# fpga_io_bank_0.net
KiCad netlist of a schematic drawn in Altium Designer
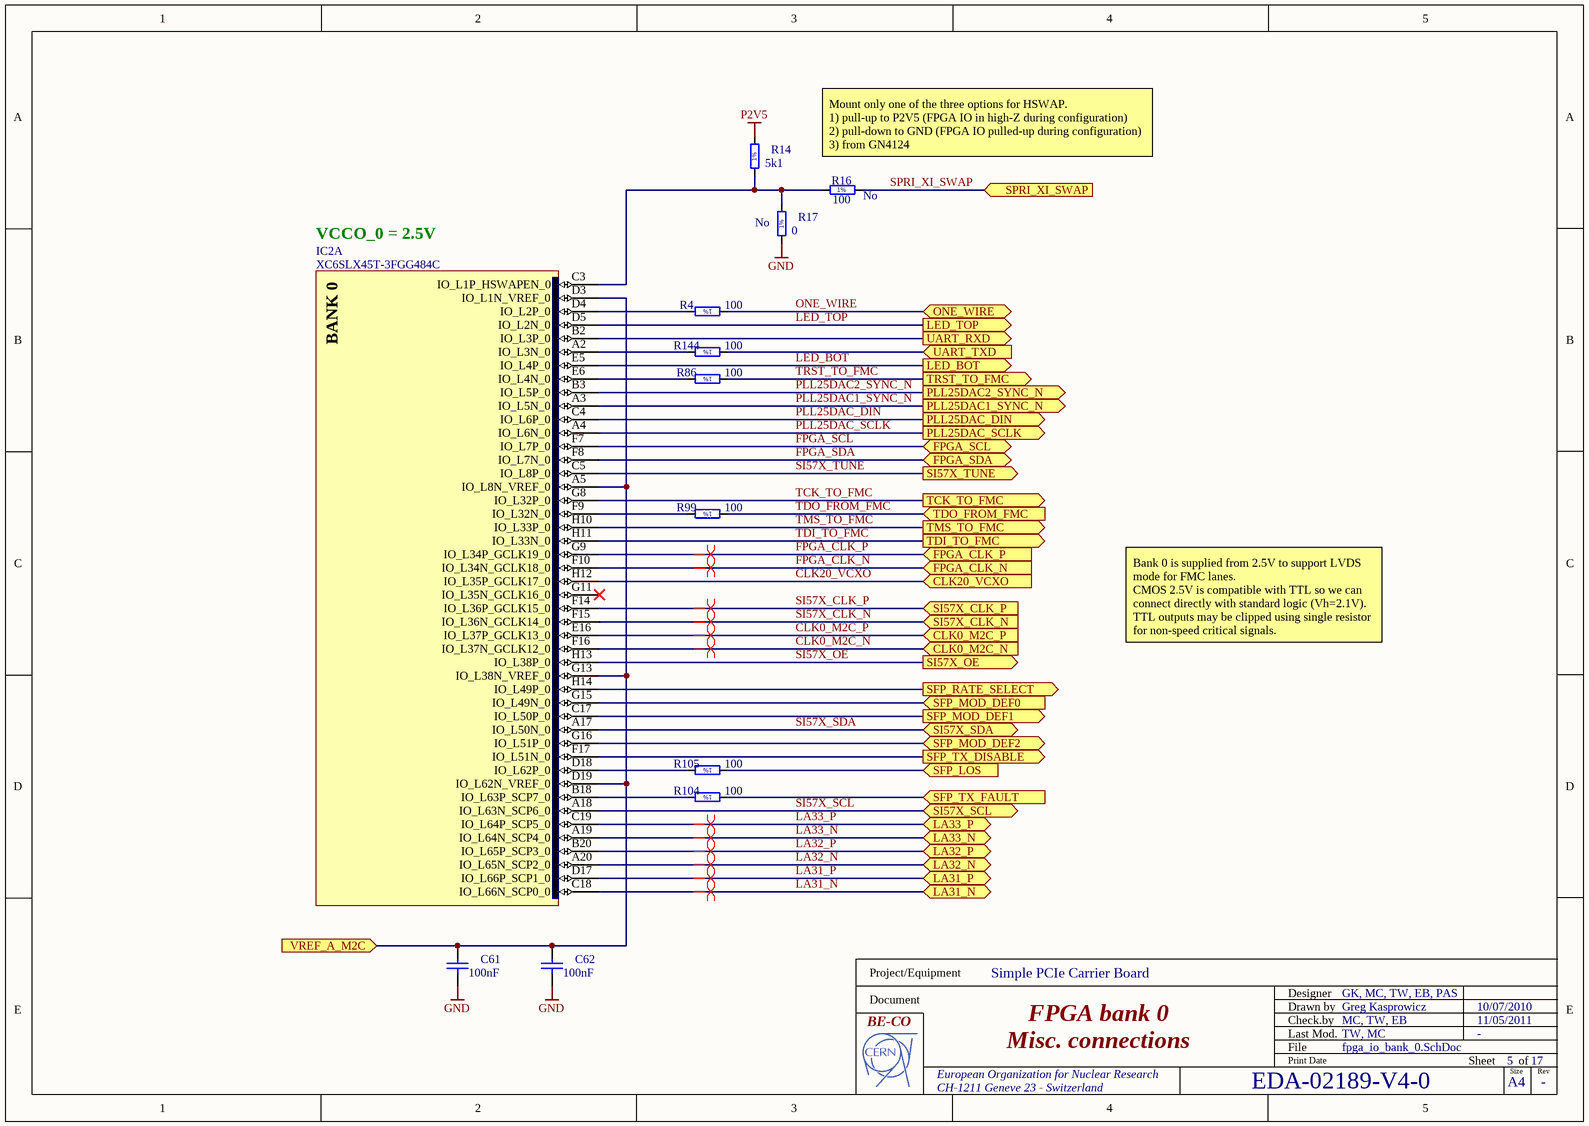
[diagram p0: fpga_io_bank_0.SchDoc]

(export (version "E")
  (design (tool "Eeschema 10.0.6"))
  (components
    (comp (ref "C61")
      (value "100nF")
      (footprint "CAPC1005X55N")
      (description "Non-polarised capacitor")
      (fields
        (field (name "PART NUMBER") "CC0402_100NF_16V_10%_X7R")
        (field (name "VOLTAGE") "16V")
        (field (name "AUTHOR") "CERN DEM JLC")
      )
      (libsource (lib "Capacitors") (part "Capacitor - non polarized"))
    )
    (comp (ref "C62")
      (value "100nF")
      (footprint "CAPC1005X55N")
      (description "Non-polarised capacitor")
      (fields
        (field (name "PART NUMBER") "CC0402_100NF_16V_10%_X7R")
        (field (name "VOLTAGE") "16V")
        (field (name "AUTHOR") "CERN DEM JLC")
      )
      (libsource (lib "Capacitors") (part "Capacitor - non polarized"))
    )
    (comp (ref "IC2")
      (value "XC6SLX45T-3FGG484C")
      (footprint "BGA484C100P22X22_2300X2300X260")
      (fields (field (name "MANUFACTURER") "XILINX") (field (name "AUTHOR") "CERN DEM JLC"))
      (libsource (lib "ICs And Semiconductors") (part "XC6SLX45T-3FGG484C"))
    )
    (comp (ref "R4")
      (value "100")
      (footprint "RESC1608X55N")
      (description "Resistor - 1%")
      (fields
        (field (name "PART NUMBER") "R0603_100R_1%_0.1W_100PPM")
        (field (name "POWER") "0.1W")
        (field (name "AUTHOR") "CERN DEM JLC")
      )
      (libsource (lib "Resistors") (part "Resistor - 1%"))
    )
    (comp (ref "R14")
      (value "5k1")
      (footprint "RESC1608X55N")
      (description "Resistor - 1%")
      (fields
        (field (name "PART NUMBER") "R0603_5K1_1%_0.1W_100PPM")
        (field (name "POWER") "0.1W")
        (field (name "AUTHOR") "CERN DEM JLC")
      )
      (libsource (lib "Resistors") (part "Resistor - 1%"))
    )
    (comp (ref "R16")
      (value "100")
      (footprint "RESC1608X55N")
      (description "Resistor - 1%")
      (fields
        (field (name "PART NUMBER") "R0603_100R_1%_0.1W_100PPM")
        (field (name "POWER") "0.1W")
        (field (name "MOUNTED") "No")
        (field (name "AUTHOR") "CERN DEM JLC")
      )
      (libsource (lib "Resistors") (part "Resistor - 1%"))
    )
    (comp (ref "R17")
      (value "0")
      (footprint "RESC1608X55N")
      (description "Resistor - 1%")
      (fields
        (field (name "PART NUMBER") "R0603_0R_JUMPER")
        (field (name "MANUFACTURER") "GENERIC")
        (field (name "MOUNTED") "No")
        (field (name "AUTHOR") "CERN DEM JLC")
      )
      (libsource (lib "Resistors") (part "Resistor - 1%"))
    )
    (comp (ref "R86")
      (value "100")
      (footprint "RESC1608X55N")
      (description "Resistor - 1%")
      (fields
        (field (name "PART NUMBER") "R0603_100R_1%_0.1W_100PPM")
        (field (name "POWER") "0.1W")
        (field (name "AUTHOR") "CERN DEM JLC")
      )
      (libsource (lib "Resistors") (part "Resistor - 1%"))
    )
    (comp (ref "R99")
      (value "100")
      (footprint "RESC1608X55N")
      (description "Resistor - 1%")
      (fields
        (field (name "PART NUMBER") "R0603_100R_1%_0.1W_100PPM")
        (field (name "POWER") "0.1W")
        (field (name "AUTHOR") "CERN DEM JLC")
      )
      (libsource (lib "Resistors") (part "Resistor - 1%"))
    )
    (comp (ref "R104")
      (value "100")
      (footprint "RESC1608X55N")
      (description "Resistor - 1%")
      (fields
        (field (name "PART NUMBER") "R0603_100R_1%_0.1W_100PPM")
        (field (name "POWER") "0.1W")
        (field (name "AUTHOR") "CERN DEM JLC")
      )
      (libsource (lib "Resistors") (part "Resistor - 1%"))
    )
    (comp (ref "R105")
      (value "100")
      (footprint "RESC1608X55N")
      (description "Resistor - 1%")
      (fields
        (field (name "PART NUMBER") "R0603_100R_1%_0.1W_100PPM")
        (field (name "POWER") "0.1W")
        (field (name "AUTHOR") "CERN DEM JLC")
      )
      (libsource (lib "Resistors") (part "Resistor - 1%"))
    )
    (comp (ref "R144")
      (value "100")
      (footprint "RESC1608X55N")
      (description "Resistor - 1%")
      (fields
        (field (name "PART NUMBER") "R0603_100R_1%_0.1W_100PPM")
        (field (name "POWER") "0.1W")
        (field (name "AUTHOR") "CERN DEM JLC")
      )
      (libsource (lib "Resistors") (part "Resistor - 1%"))
    )
  )
  (nets
    (net (code "1") (name "/CLK0_M2C_N") (class "Default")
      (node (ref "IC2") (pin "F16") (pinfunction "IO_L37N_GCLK12_0_F16") (pintype "bidirectional"))
    )
    (net (code "2") (name "/CLK0_M2C_P") (class "Default")
      (node (ref "IC2") (pin "E16") (pinfunction "IO_L37P_GCLK13_0_E16") (pintype "bidirectional"))
    )
    (net (code "3") (name "/CLK20_VCXO") (class "Default")
      (node (ref "IC2") (pin "H12") (pinfunction "IO_L35P_GCLK17_0_H12") (pintype "bidirectional"))
    )
    (net (code "4") (name "/FPGA_CLK_N") (class "Default")
      (node (ref "IC2") (pin "F10") (pinfunction "IO_L34N_GCLK18_0_F10") (pintype "bidirectional"))
    )
    (net (code "5") (name "/FPGA_CLK_P") (class "Default")
      (node (ref "IC2") (pin "G9") (pinfunction "IO_L34P_GCLK19_0_G9") (pintype "bidirectional"))
    )
    (net (code "6") (name "/FPGA_SCL") (class "Default")
      (node (ref "IC2") (pin "F7") (pinfunction "IO_L7P_0_F7") (pintype "bidirectional"))
    )
    (net (code "7") (name "/FPGA_SDA") (class "Default")
      (node (ref "IC2") (pin "F8") (pinfunction "IO_L7N_0_F8") (pintype "bidirectional"))
    )
    (net (code "8") (name "/LA31_N") (class "Default")
      (node (ref "IC2") (pin "C18") (pinfunction "IO_L66N_SCP0_0_C18") (pintype "bidirectional"))
    )
    (net (code "9") (name "/LA31_P") (class "Default")
      (node (ref "IC2") (pin "D17") (pinfunction "IO_L66P_SCP1_0_D17") (pintype "bidirectional"))
    )
    (net (code "10") (name "/LA32_N") (class "Default")
      (node (ref "IC2") (pin "A20") (pinfunction "IO_L65N_SCP2_0_A20") (pintype "bidirectional"))
    )
    (net (code "11") (name "/LA32_P") (class "Default")
      (node (ref "IC2") (pin "B20") (pinfunction "IO_L65P_SCP3_0_B20") (pintype "bidirectional"))
    )
    (net (code "12") (name "/LA33_N") (class "Default")
      (node (ref "IC2") (pin "A19") (pinfunction "IO_L64N_SCP4_0_A19") (pintype "bidirectional"))
    )
    (net (code "13") (name "/LA33_P") (class "Default")
      (node (ref "IC2") (pin "C19") (pinfunction "IO_L64P_SCP5_0_C19") (pintype "bidirectional"))
    )
    (net (code "14") (name "/LED_BOT") (class "Default")
      (node (ref "IC2") (pin "E5") (pinfunction "IO_L4P_0_E5") (pintype "bidirectional"))
    )
    (net (code "15") (name "/LED_TOP") (class "Default")
      (node (ref "IC2") (pin "D5") (pinfunction "IO_L2N_0_D5") (pintype "bidirectional"))
    )
    (net (code "16") (name "/ONE_WIRE") (class "Default")
      (node (ref "R4") (pin "1") (pinfunction "1_1") (pintype "passive"))
    )
    (net (code "17") (name "/PLL25DAC1_SYNC_N") (class "Default")
      (node (ref "IC2") (pin "A3") (pinfunction "IO_L5N_0_A3") (pintype "bidirectional"))
    )
    (net (code "18") (name "/PLL25DAC2_SYNC_N") (class "Default")
      (node (ref "IC2") (pin "B3") (pinfunction "IO_L5P_0_B3") (pintype "bidirectional"))
    )
    (net (code "19") (name "/PLL25DAC_DIN") (class "Default")
      (node (ref "IC2") (pin "C4") (pinfunction "IO_L6P_0_C4") (pintype "bidirectional"))
    )
    (net (code "20") (name "/PLL25DAC_SCLK") (class "Default")
      (node (ref "IC2") (pin "A4") (pinfunction "IO_L6N_0_A4") (pintype "bidirectional"))
    )
    (net (code "21") (name "/SFP_LOS") (class "Default")
      (node (ref "R105") (pin "1") (pinfunction "1_1") (pintype "passive"))
    )
    (net (code "22") (name "/SFP_MOD_DEF0") (class "Default")
      (node (ref "IC2") (pin "G15") (pinfunction "IO_L49N_0_G15") (pintype "bidirectional"))
    )
    (net (code "23") (name "/SFP_MOD_DEF1") (class "Default")
      (node (ref "IC2") (pin "C17") (pinfunction "IO_L50P_0_C17") (pintype "bidirectional"))
    )
    (net (code "24") (name "/SFP_MOD_DEF2") (class "Default")
      (node (ref "IC2") (pin "G16") (pinfunction "IO_L51P_0_G16") (pintype "bidirectional"))
    )
    (net (code "25") (name "/SFP_RATE_SELECT") (class "Default")
      (node (ref "IC2") (pin "H14") (pinfunction "IO_L49P_0_H14") (pintype "bidirectional"))
    )
    (net (code "26") (name "/SFP_TX_DISABLE") (class "Default")
      (node (ref "IC2") (pin "F17") (pinfunction "IO_L51N_0_F17") (pintype "bidirectional"))
    )
    (net (code "27") (name "/SFP_TX_FAULT") (class "Default")
      (node (ref "R104") (pin "1") (pinfunction "1_1") (pintype "passive"))
    )
    (net (code "28") (name "/SI57X_CLK_N") (class "Default")
      (node (ref "IC2") (pin "F15") (pinfunction "IO_L36N_GCLK14_0_F15") (pintype "bidirectional"))
    )
    (net (code "29") (name "/SI57X_CLK_P") (class "Default")
      (node (ref "IC2") (pin "F14") (pinfunction "IO_L36P_GCLK15_0_F14") (pintype "bidirectional"))
    )
    (net (code "30") (name "/SI57X_OE") (class "Default")
      (node (ref "IC2") (pin "H13") (pinfunction "IO_L38P_0_H13") (pintype "bidirectional"))
    )
    (net (code "31") (name "/SI57X_SCL") (class "Default")
      (node (ref "IC2") (pin "A18") (pinfunction "IO_L63N_SCP6_0_A18") (pintype "bidirectional"))
    )
    (net (code "32") (name "/SI57X_SDA") (class "Default")
      (node (ref "IC2") (pin "A17") (pinfunction "IO_L50N_0_A17") (pintype "bidirectional"))
    )
    (net (code "33") (name "/SI57X_TUNE") (class "Default")
      (node (ref "IC2") (pin "C5") (pinfunction "IO_L8P_0_C5") (pintype "bidirectional"))
    )
    (net (code "34") (name "/SPRI_XI_SWAP") (class "Default")
      (node (ref "R16") (pin "2") (pinfunction "2_2") (pintype "passive"))
    )
    (net (code "35") (name "/TCK_TO_FMC") (class "Default")
      (node (ref "IC2") (pin "G8") (pinfunction "IO_L32P_0_G8") (pintype "bidirectional"))
    )
    (net (code "36") (name "/TDI_TO_FMC") (class "Default")
      (node (ref "IC2") (pin "H11") (pinfunction "IO_L33N_0_H11") (pintype "bidirectional"))
    )
    (net (code "37") (name "/TDO_FROM_FMC") (class "Default")
      (node (ref "R99") (pin "1") (pinfunction "1_1") (pintype "passive"))
    )
    (net (code "38") (name "/TMS_TO_FMC") (class "Default")
      (node (ref "IC2") (pin "H10") (pinfunction "IO_L33P_0_H10") (pintype "bidirectional"))
    )
    (net (code "39") (name "/TRST_TO_FMC") (class "Default")
      (node (ref "R86") (pin "1") (pinfunction "1_1") (pintype "passive"))
    )
    (net (code "40") (name "/UART_RXD") (class "Default")
      (node (ref "IC2") (pin "B2") (pinfunction "IO_L3P_0_B2") (pintype "bidirectional"))
    )
    (net (code "41") (name "/UART_TXD") (class "Default")
      (node (ref "R144") (pin "1") (pinfunction "1_1") (pintype "passive"))
    )
    (net (code "42") (name "/VREF_A_M2C") (class "Default")
      (node (ref "C61") (pin "2") (pinfunction "2_2") (pintype "passive"))
      (node (ref "C62") (pin "2") (pinfunction "2_2") (pintype "passive"))
      (node (ref "IC2") (pin "A5") (pinfunction "IO_L8N_VREF_0_A5") (pintype "bidirectional"))
      (node (ref "IC2") (pin "D19") (pinfunction "IO_L62N_VREF_0_D19") (pintype "bidirectional"))
      (node (ref "IC2") (pin "D3") (pinfunction "IO_L1N_VREF_0_D3") (pintype "bidirectional"))
      (node (ref "IC2") (pin "G13") (pinfunction "IO_L38N_VREF_0_G13") (pintype "bidirectional"))
    )
    (net (code "43") (name "GND") (class "Default")
      (node (ref "C61") (pin "1") (pinfunction "1_1") (pintype "passive"))
      (node (ref "C62") (pin "1") (pinfunction "1_1") (pintype "passive"))
      (node (ref "R17") (pin "1") (pinfunction "1_1") (pintype "passive"))
    )
    (net (code "44") (name "Net-(IC2A-IO_L1P_HSWAPEN_0)") (class "Default")
      (node (ref "IC2") (pin "C3") (pinfunction "IO_L1P_HSWAPEN_0_C3") (pintype "bidirectional"))
      (node (ref "R14") (pin "1") (pinfunction "1_1") (pintype "passive"))
      (node (ref "R16") (pin "1") (pinfunction "1_1") (pintype "passive"))
      (node (ref "R17") (pin "2") (pinfunction "2_2") (pintype "passive"))
    )
    (net (code "45") (name "Net-(IC2A-IO_L2P_0)") (class "Default")
      (node (ref "IC2") (pin "D4") (pinfunction "IO_L2P_0_D4") (pintype "bidirectional"))
      (node (ref "R4") (pin "2") (pinfunction "2_2") (pintype "passive"))
    )
    (net (code "46") (name "Net-(IC2A-IO_L3N_0)") (class "Default")
      (node (ref "IC2") (pin "A2") (pinfunction "IO_L3N_0_A2") (pintype "bidirectional"))
      (node (ref "R144") (pin "2") (pinfunction "2_2") (pintype "passive"))
    )
    (net (code "47") (name "Net-(IC2A-IO_L4N_0)") (class "Default")
      (node (ref "IC2") (pin "E6") (pinfunction "IO_L4N_0_E6") (pintype "bidirectional"))
      (node (ref "R86") (pin "2") (pinfunction "2_2") (pintype "passive"))
    )
    (net (code "48") (name "Net-(IC2A-IO_L32N_0)") (class "Default")
      (node (ref "IC2") (pin "F9") (pinfunction "IO_L32N_0_F9") (pintype "bidirectional"))
      (node (ref "R99") (pin "2") (pinfunction "2_2") (pintype "passive"))
    )
    (net (code "49") (name "Net-(IC2A-IO_L62P_0)") (class "Default")
      (node (ref "IC2") (pin "D18") (pinfunction "IO_L62P_0_D18") (pintype "bidirectional"))
      (node (ref "R105") (pin "2") (pinfunction "2_2") (pintype "passive"))
    )
    (net (code "50") (name "Net-(IC2A-IO_L63P_SCP7_0)") (class "Default")
      (node (ref "IC2") (pin "B18") (pinfunction "IO_L63P_SCP7_0_B18") (pintype "bidirectional"))
      (node (ref "R104") (pin "2") (pinfunction "2_2") (pintype "passive"))
    )
    (net (code "51") (name "P2V5") (class "Default")
      (node (ref "R14") (pin "2") (pinfunction "2_2") (pintype "passive"))
    )
    (net (code "52") (name "unconnected-(IC2A-IO_L35N_GCLK16_0-PadG11)") (class "Default")
      (node (ref "IC2") (pin "G11") (pinfunction "IO_L35N_GCLK16_0_G11") (pintype "bidirectional+no_connect"))
    )
  )
)
